# Microcontroller.net
KiCad netlist of a schematic drawn in Altium Designer
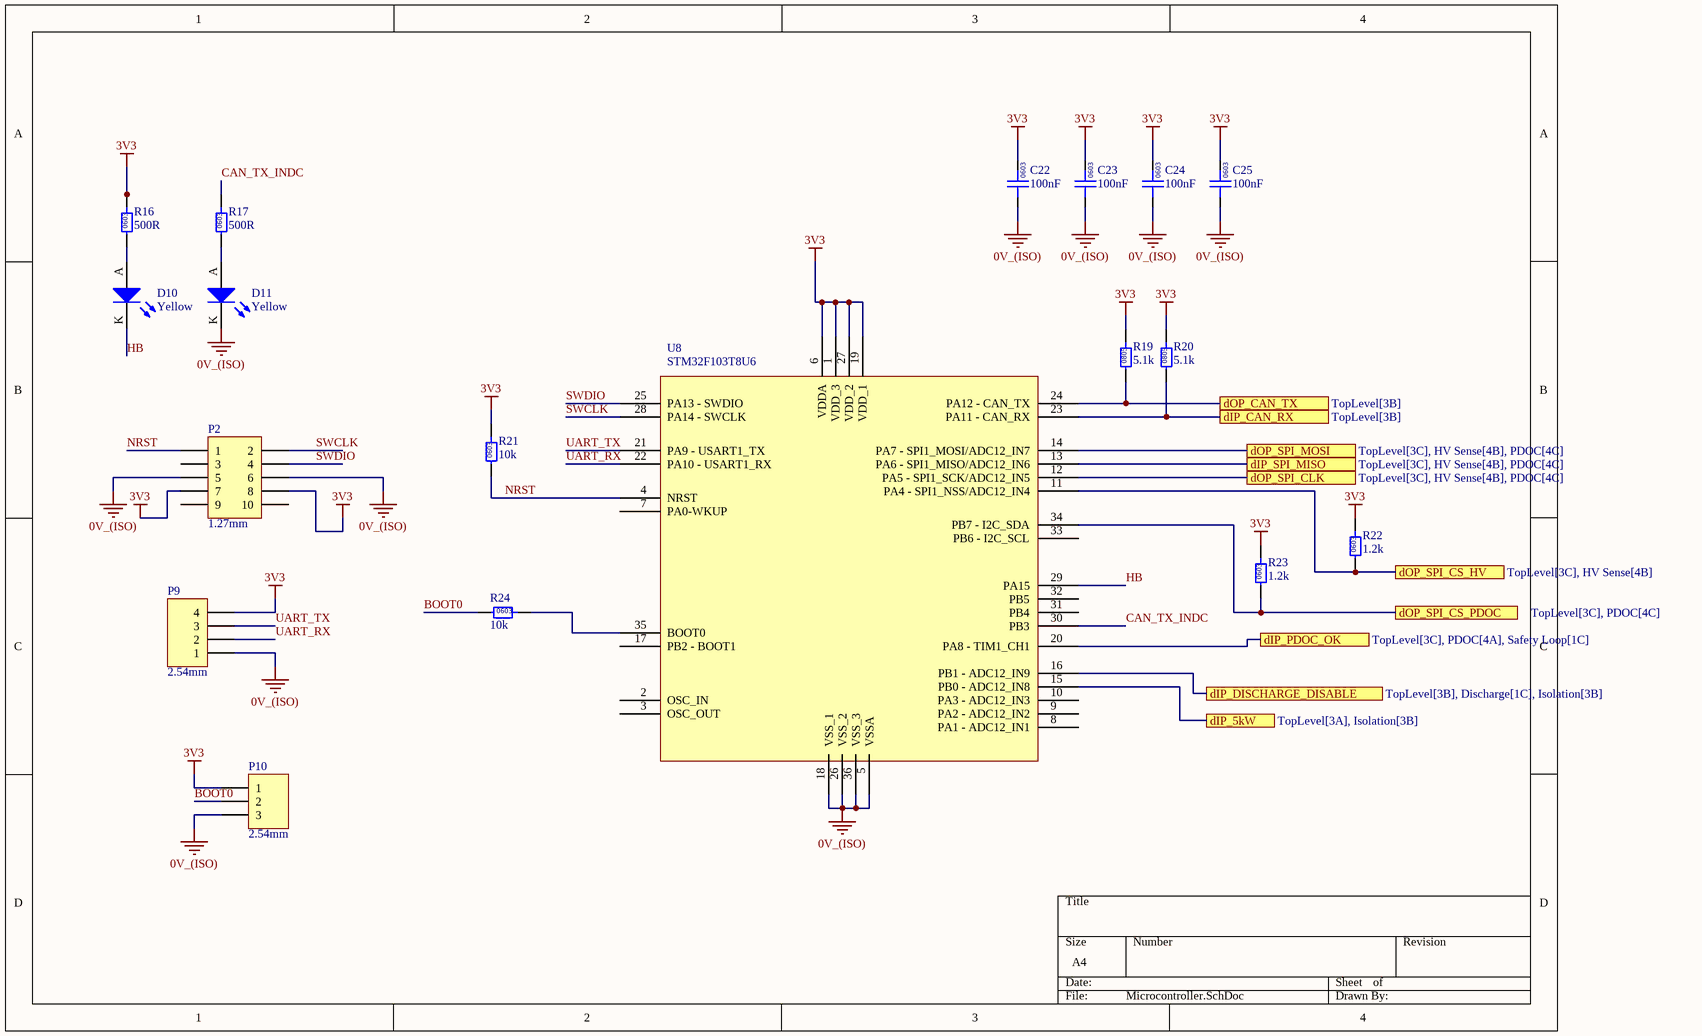
[diagram p0: Microcontroller.SchDoc]

(export (version "E")
  (design (tool "Eeschema 10.0.6"))
  (components
    (comp (ref "C22")
      (value "100nF")
      (footprint "0603")
      (fields
        (field (name "PART NUMBER") "GCM188L81H104KA57D")
        (field (name "MANUFACTURER") "muRata")
        (field (name "TOLERANCE") "±10%")
      )
      (libsource (lib "ts_standard_library") (part "Capacitor 0603"))
    )
    (comp (ref "C23")
      (value "100nF")
      (footprint "0603")
      (fields
        (field (name "PART NUMBER") "GCM188L81H104KA57D")
        (field (name "MANUFACTURER") "muRata")
        (field (name "TOLERANCE") "±10%")
      )
      (libsource (lib "ts_standard_library") (part "Capacitor 0603"))
    )
    (comp (ref "C24")
      (value "100nF")
      (footprint "0603")
      (fields
        (field (name "PART NUMBER") "GCM188L81H104KA57D")
        (field (name "MANUFACTURER") "muRata")
        (field (name "TOLERANCE") "±10%")
      )
      (libsource (lib "ts_standard_library") (part "Capacitor 0603"))
    )
    (comp (ref "C25")
      (value "100nF")
      (footprint "0603")
      (fields
        (field (name "PART NUMBER") "GCM188L81H104KA57D")
        (field (name "MANUFACTURER") "muRata")
        (field (name "TOLERANCE") "±10%")
      )
      (libsource (lib "ts_standard_library") (part "Capacitor 0603"))
    )
    (comp (ref "D10")
      (value "Yellow")
      (footprint "0805 LED")
      (description "Yellow LED Indication - Discrete 1.75V 0805 (2012 Metric)")
      (fields (field (name "PART NUMBER") "SML-211YTT86") (field (name "MANUFACTURER") "ROHM Semiconductor"))
      (libsource (lib "ts_standard_library") (part "LED"))
    )
    (comp (ref "D11")
      (value "Yellow")
      (footprint "0805 LED")
      (description "Yellow LED Indication - Discrete 1.75V 0805 (2012 Metric)")
      (fields (field (name "PART NUMBER") "SML-211YTT86") (field (name "MANUFACTURER") "ROHM Semiconductor"))
      (libsource (lib "ts_standard_library") (part "LED"))
    )
    (comp (ref "P2")
      (value "1.27mm")
      (footprint "3221-10-0300-00")
      (fields
        (field (name "PART NUMBER") "SMD 1.27mm Header 2x5 (3221-10-0300-00)")
        (field (name "CONTACT") "NA")
      )
      (libsource (lib "ts_standard_connectors") (part "Header 2x5"))
    )
    (comp (ref "P9")
      (value "2.54mm")
      (footprint "TH 2.54mm Header 1x4")
      (fields (field (name "PART NUMBER") "TH 2.54mm Header 1x4") (field (name "CONTACT") "NA"))
      (libsource (lib "ts_standard_connectors") (part "Header 1x4"))
    )
    (comp (ref "P10")
      (value "2.54mm")
      (footprint "TH 2.54mm Header 1x3")
      (fields (field (name "PART NUMBER") "TH 2.54mm Header 1x3") (field (name "CONTACT") "NA"))
      (libsource (lib "ts_standard_connectors") (part "Header 1x3"))
    )
    (comp (ref "R16")
      (value "500R")
      (footprint "0603")
      (fields
        (field (name "PART NUMBER") "RT0603BRD07500RL")
        (field (name "MANUFACTURER") "YAGEO")
        (field (name "TOLERANCE") "0.01")
      )
      (libsource (lib "ts_standard_library") (part "Resistor 0603"))
    )
    (comp (ref "R17")
      (value "500R")
      (footprint "0603")
      (fields
        (field (name "PART NUMBER") "RT0603BRD07500RL")
        (field (name "MANUFACTURER") "YAGEO")
        (field (name "TOLERANCE") "0.01")
      )
      (libsource (lib "ts_standard_library") (part "Resistor 0603"))
    )
    (comp (ref "R19")
      (value "5.1k")
      (footprint "0805")
      (fields
        (field (name "PART NUMBER") "RC0805FR075K1L")
        (field (name "MANUFACTURER") "YAGEO")
        (field (name "TOLERANCE") "0.01")
      )
      (libsource (lib "ts_standard_library") (part "Resistor 0805"))
    )
    (comp (ref "R20")
      (value "5.1k")
      (footprint "0805")
      (fields
        (field (name "PART NUMBER") "RC0805FR075K1L")
        (field (name "MANUFACTURER") "YAGEO")
        (field (name "TOLERANCE") "0.01")
      )
      (libsource (lib "ts_standard_library") (part "Resistor 0805"))
    )
    (comp (ref "R21")
      (value "10k")
      (footprint "0603")
      (fields
        (field (name "PART NUMBER") "RC0603FR-0710KL")
        (field (name "MANUFACTURER") "YAGEO")
        (field (name "TOLERANCE") "0.01")
      )
      (libsource (lib "ts_standard_library") (part "Resistor 0603"))
    )
    (comp (ref "R22")
      (value "1.2k")
      (footprint "0603")
      (fields
        (field (name "PART NUMBER") "RC0603JR-071K2L")
        (field (name "MANUFACTURER") "YAGEO")
        (field (name "TOLERANCE") "0.01")
      )
      (libsource (lib "ts_standard_library") (part "Resistor 0603"))
    )
    (comp (ref "R23")
      (value "1.2k")
      (footprint "0603")
      (fields
        (field (name "PART NUMBER") "RC0603JR-071K2L")
        (field (name "MANUFACTURER") "YAGEO")
        (field (name "TOLERANCE") "0.01")
      )
      (libsource (lib "ts_standard_library") (part "Resistor 0603"))
    )
    (comp (ref "R24")
      (value "10k")
      (footprint "0603")
      (fields
        (field (name "PART NUMBER") "RC0603FR-0710KL")
        (field (name "MANUFACTURER") "YAGEO")
        (field (name "TOLERANCE") "0.01")
      )
      (libsource (lib "ts_standard_library") (part "Resistor 0603"))
    )
    (comp (ref "U8")
      (value "STM32F103T8U6")
      (footprint "STM_QFN-36")
      (description "ARM® Cortex®-M3 STM32F1 Microcontroller IC 32-Bit 72MHz 64KB (64K x 8) FLASH QFN")
      (fields (field (name "MANUFACTURER") "ST Microelectronics"))
      (libsource (lib "ts_standard_library") (part "STM32F103T8U6"))
    )
  )
  (nets
    (net (code "1") (name "/BOOT0") (class "Default")
      (node (ref "P10") (pin "2") (pinfunction "2_2") (pintype "passive"))
      (node (ref "R24") (pin "1") (pinfunction "1_1") (pintype "passive"))
    )
    (net (code "2") (name "/CAN_TX_INDC") (class "Default")
      (node (ref "R17") (pin "2") (pinfunction "2_2") (pintype "passive"))
      (node (ref "U8") (pin "30") (pinfunction "PB3_30") (pintype "passive"))
    )
    (net (code "3") (name "/HB") (class "Default")
      (node (ref "D10") (pin "K") (pinfunction "K_K") (pintype "passive"))
      (node (ref "U8") (pin "29") (pinfunction "PA15_29") (pintype "passive"))
    )
    (net (code "4") (name "/NRST") (class "Default")
      (node (ref "P2") (pin "1") (pinfunction "1_1") (pintype "passive"))
      (node (ref "R21") (pin "1") (pinfunction "1_1") (pintype "passive"))
      (node (ref "U8") (pin "4") (pinfunction "NRST_4") (pintype "passive"))
    )
    (net (code "5") (name "/SWCLK") (class "Default")
      (node (ref "P2") (pin "2") (pinfunction "2_2") (pintype "passive"))
      (node (ref "U8") (pin "28") (pinfunction "PA14_-_SWCLK_28") (pintype "passive"))
    )
    (net (code "6") (name "/SWDIO") (class "Default")
      (node (ref "P2") (pin "4") (pinfunction "4_4") (pintype "passive"))
      (node (ref "U8") (pin "25") (pinfunction "PA13_-_SWDIO_25") (pintype "passive"))
    )
    (net (code "7") (name "/UART_RX") (class "Default")
      (node (ref "P9") (pin "2") (pinfunction "2_2") (pintype "passive"))
      (node (ref "U8") (pin "22") (pinfunction "PA10_-_USART1_RX_22") (pintype "passive"))
    )
    (net (code "8") (name "/UART_TX") (class "Default")
      (node (ref "P9") (pin "3") (pinfunction "3_3") (pintype "passive"))
      (node (ref "U8") (pin "21") (pinfunction "PA9_-_USART1_TX_21") (pintype "passive"))
    )
    (net (code "9") (name "/dIP_5kW") (class "Default")
      (node (ref "U8") (pin "15") (pinfunction "PB0_-_ADC12_IN8_15") (pintype "passive"))
    )
    (net (code "10") (name "/dIP_CAN_RX") (class "Default")
      (node (ref "R20") (pin "1") (pinfunction "1_1") (pintype "passive"))
      (node (ref "U8") (pin "23") (pinfunction "PA11_-_CAN_RX_23") (pintype "passive"))
    )
    (net (code "11") (name "/dIP_DISCHARGE_DISABLE") (class "Default")
      (node (ref "U8") (pin "16") (pinfunction "PB1_-_ADC12_IN9_16") (pintype "passive"))
    )
    (net (code "12") (name "/dIP_PDOC_OK") (class "Default")
      (node (ref "U8") (pin "20") (pinfunction "PA8_-_TIM1_CH1_20") (pintype "passive"))
    )
    (net (code "13") (name "/dIP_SPI_MISO") (class "Default")
      (node (ref "U8") (pin "13") (pinfunction "PA6_-_SPI1_MISO/ADC12_IN6_13") (pintype "passive"))
    )
    (net (code "14") (name "/dOP_CAN_TX") (class "Default")
      (node (ref "R19") (pin "1") (pinfunction "1_1") (pintype "passive"))
      (node (ref "U8") (pin "24") (pinfunction "PA12_-_CAN_TX_24") (pintype "passive"))
    )
    (net (code "15") (name "/dOP_SPI_CLK") (class "Default")
      (node (ref "U8") (pin "12") (pinfunction "PA5_-_SPI1_SCK/ADC12_IN5_12") (pintype "passive"))
    )
    (net (code "16") (name "/dOP_SPI_CS_HV") (class "Default")
      (node (ref "R22") (pin "1") (pinfunction "1_1") (pintype "passive"))
      (node (ref "U8") (pin "11") (pinfunction "PA4_-_SPI1_NSS/ADC12_IN4_11") (pintype "passive"))
    )
    (net (code "17") (name "/dOP_SPI_CS_PDOC") (class "Default")
      (node (ref "R23") (pin "1") (pinfunction "1_1") (pintype "passive"))
      (node (ref "U8") (pin "34") (pinfunction "PB7_-_I2C_SDA_34") (pintype "passive"))
    )
    (net (code "18") (name "/dOP_SPI_MOSI") (class "Default")
      (node (ref "U8") (pin "14") (pinfunction "PA7_-_SPI1_MOSI/ADC12_IN7_14") (pintype "passive"))
    )
    (net (code "19") (name "0V_(ISO)") (class "Default")
      (node (ref "C22") (pin "1") (pinfunction "1_1") (pintype "passive"))
      (node (ref "C23") (pin "1") (pinfunction "1_1") (pintype "passive"))
      (node (ref "C24") (pin "1") (pinfunction "1_1") (pintype "passive"))
      (node (ref "C25") (pin "1") (pinfunction "1_1") (pintype "passive"))
      (node (ref "D11") (pin "K") (pinfunction "K_K") (pintype "passive"))
      (node (ref "P10") (pin "3") (pinfunction "3_3") (pintype "passive"))
      (node (ref "P2") (pin "5") (pinfunction "5_5") (pintype "passive"))
      (node (ref "P2") (pin "6") (pinfunction "6_6") (pintype "passive"))
      (node (ref "P9") (pin "1") (pinfunction "1_1") (pintype "passive"))
      (node (ref "U8") (pin "18") (pinfunction "VSS_1_18") (pintype "passive"))
      (node (ref "U8") (pin "26") (pinfunction "VSS_2_26") (pintype "passive"))
      (node (ref "U8") (pin "36") (pinfunction "VSS_3_36") (pintype "passive"))
      (node (ref "U8") (pin "5") (pinfunction "VSSA_5") (pintype "passive"))
    )
    (net (code "20") (name "3V3") (class "Default")
      (node (ref "C22") (pin "2") (pinfunction "2_2") (pintype "passive"))
      (node (ref "C23") (pin "2") (pinfunction "2_2") (pintype "passive"))
      (node (ref "C24") (pin "2") (pinfunction "2_2") (pintype "passive"))
      (node (ref "C25") (pin "2") (pinfunction "2_2") (pintype "passive"))
      (node (ref "P10") (pin "1") (pinfunction "1_1") (pintype "passive"))
      (node (ref "P2") (pin "7") (pinfunction "7_7") (pintype "passive"))
      (node (ref "P2") (pin "8") (pinfunction "8_8") (pintype "passive"))
      (node (ref "P9") (pin "4") (pinfunction "4_4") (pintype "passive"))
      (node (ref "R16") (pin "2") (pinfunction "2_2") (pintype "passive"))
      (node (ref "R19") (pin "2") (pinfunction "2_2") (pintype "passive"))
      (node (ref "R20") (pin "2") (pinfunction "2_2") (pintype "passive"))
      (node (ref "R21") (pin "2") (pinfunction "2_2") (pintype "passive"))
      (node (ref "R22") (pin "2") (pinfunction "2_2") (pintype "passive"))
      (node (ref "R23") (pin "2") (pinfunction "2_2") (pintype "passive"))
      (node (ref "U8") (pin "1") (pinfunction "VDD_3_1") (pintype "passive"))
      (node (ref "U8") (pin "19") (pinfunction "VDD_1_19") (pintype "passive"))
      (node (ref "U8") (pin "27") (pinfunction "VDD_2_27") (pintype "passive"))
      (node (ref "U8") (pin "6") (pinfunction "VDDA_6") (pintype "passive"))
    )
    (net (code "21") (name "Net-(D10-PadA)") (class "Default")
      (node (ref "D10") (pin "A") (pinfunction "A_A") (pintype "passive"))
      (node (ref "R16") (pin "1") (pinfunction "1_1") (pintype "passive"))
    )
    (net (code "22") (name "Net-(D11-PadA)") (class "Default")
      (node (ref "D11") (pin "A") (pinfunction "A_A") (pintype "passive"))
      (node (ref "R17") (pin "1") (pinfunction "1_1") (pintype "passive"))
    )
    (net (code "23") (name "Net-(U8-BOOT0)") (class "Default")
      (node (ref "R24") (pin "2") (pinfunction "2_2") (pintype "passive"))
      (node (ref "U8") (pin "35") (pinfunction "BOOT0_35") (pintype "passive"))
    )
    (net (code "24") (name "unconnected-(P2-Pad3)") (class "Default")
      (node (ref "P2") (pin "3") (pinfunction "3_3") (pintype "passive"))
    )
    (net (code "25") (name "unconnected-(P2-Pad9)") (class "Default")
      (node (ref "P2") (pin "9") (pinfunction "9_9") (pintype "passive"))
    )
    (net (code "26") (name "unconnected-(P2-Pad10)") (class "Default")
      (node (ref "P2") (pin "10") (pinfunction "10_10") (pintype "passive"))
    )
    (net (code "27") (name "unconnected-(U8-OSC_IN-Pad2)") (class "Default")
      (node (ref "U8") (pin "2") (pinfunction "OSC_IN_2") (pintype "passive"))
    )
    (net (code "28") (name "unconnected-(U8-OSC_OUT-Pad3)") (class "Default")
      (node (ref "U8") (pin "3") (pinfunction "OSC_OUT_3") (pintype "passive"))
    )
    (net (code "29") (name "unconnected-(U8-PA0-WKUP-Pad7)") (class "Default")
      (node (ref "U8") (pin "7") (pinfunction "PA0-WKUP_7") (pintype "passive"))
    )
    (net (code "30") (name "unconnected-(U8-PA1_-_ADC12_IN1-Pad8)") (class "Default")
      (node (ref "U8") (pin "8") (pinfunction "PA1_-_ADC12_IN1_8") (pintype "passive"))
    )
    (net (code "31") (name "unconnected-(U8-PA2_-_ADC12_IN2-Pad9)") (class "Default")
      (node (ref "U8") (pin "9") (pinfunction "PA2_-_ADC12_IN2_9") (pintype "passive"))
    )
    (net (code "32") (name "unconnected-(U8-PA3_-_ADC12_IN3-Pad10)") (class "Default")
      (node (ref "U8") (pin "10") (pinfunction "PA3_-_ADC12_IN3_10") (pintype "passive"))
    )
    (net (code "33") (name "unconnected-(U8-PB2_-_BOOT1-Pad17)") (class "Default")
      (node (ref "U8") (pin "17") (pinfunction "PB2_-_BOOT1_17") (pintype "passive"))
    )
    (net (code "34") (name "unconnected-(U8-PB4-Pad31)") (class "Default")
      (node (ref "U8") (pin "31") (pinfunction "PB4_31") (pintype "passive"))
    )
    (net (code "35") (name "unconnected-(U8-PB5-Pad32)") (class "Default")
      (node (ref "U8") (pin "32") (pinfunction "PB5_32") (pintype "passive"))
    )
    (net (code "36") (name "unconnected-(U8-PB6_-_I2C_SCL-Pad33)") (class "Default")
      (node (ref "U8") (pin "33") (pinfunction "PB6_-_I2C_SCL_33") (pintype "passive"))
    )
  )
)
